# Controller-Sheet.net
KiCad netlist of a schematic drawn in Altium Designer
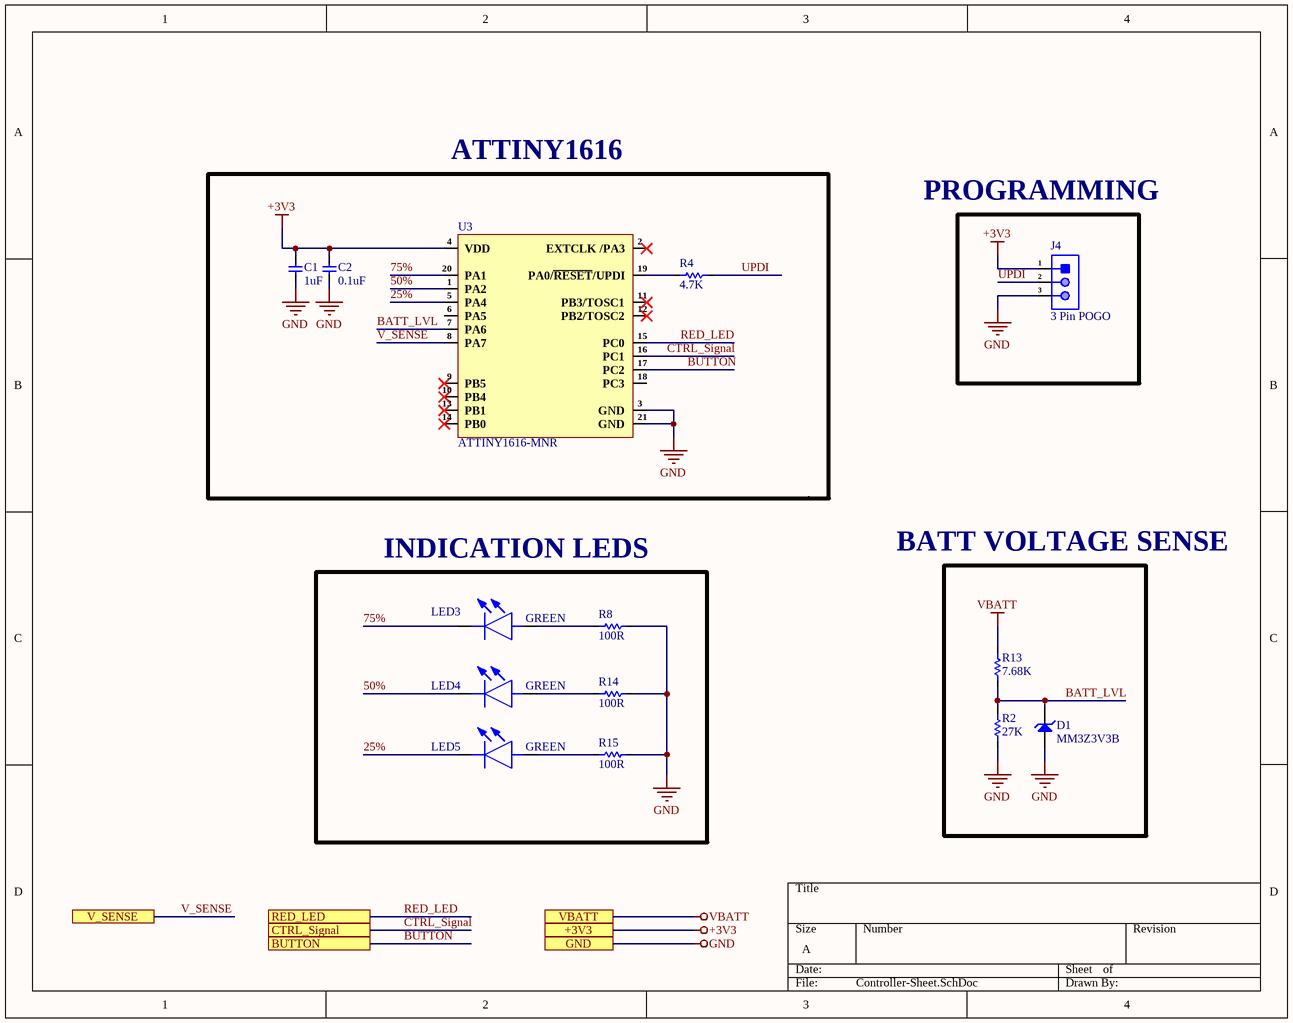
[diagram p0: Controller-Sheet.SchDoc]

(export (version "E")
  (design (tool "Eeschema 10.0.6"))
  (components
    (comp (ref "C1")
      (value "1uF")
      (footprint "Cap-0402")
      (description "1 µF ±20% 6.3V Ceramic Capacitor X5R 0201 (0603 Metric)")
      (fields
        (field (name "MANUFACTURER") "Murata Electronics")
        (field (name "MANUFACTURER PART NUMBER") "GRM033R60J105MEA2D")
      )
      (libsource (lib "LED-Driver-Library") (part "GRM033R60J105MEA2D"))
    )
    (comp (ref "C2")
      (value "0.1uF")
      (footprint "Cap-0402")
      (description "0.1 µF ±10% 16V Ceramic Capacitor X7R 0402 (1005 Metric)")
      (fields
        (field (name "MANUFACTURER") "Murata Electronics")
        (field (name "MANUFACTURER PART NUMBER") "GRM155R71C104KA88J")
      )
      (libsource (lib "LED-Driver-Library") (part "GRM155R71C104KA88J"))
    )
    (comp (ref "D1")
      (value "MM3Z3V3B")
      (footprint "SOD323F")
      (description "DIODE ZENER 3.3V 200MW SOD323F")
      (fields (field (name "MANUFACTURER") "ON Semiconductor / Fairchild") (field (name "TOLERANCE") "2%"))
      (libsource (lib "LED-Driver-Library") (part "MM3Z3V3B"))
    )
    (comp (ref "J4")
      (value "3 Pin POGO")
      (footprint "3 Pin POGO")
      (description "CONN HEADER VERT 3POS 2.54MM")
      (fields (field (name "LCSC PART NUMBER") "C168677") (field (name "DIGIKEY PART NUMBER") "609-3461-ND"))
      (libsource (lib "LED-Driver-Library") (part "68000-103HLF"))
    )
    (comp (ref "LED3")
      (value "GREEN")
      (footprint "150060GS75000")
      (description "Green 520nm LED Indication - Discrete 3.2V 0603 (1608 Metric)")
      (fields
        (field (name "MANUFACTURER") "Würth Elektronik")
        (field (name "MANUFACTURER PART NUMBER") "150060GS75000")
      )
      (libsource (lib "LED-Driver-Library") (part "150060GS75000"))
    )
    (comp (ref "LED4")
      (value "GREEN")
      (footprint "150060GS75000")
      (description "Green 520nm LED Indication - Discrete 3.2V 0603 (1608 Metric)")
      (fields
        (field (name "MANUFACTURER") "Würth Elektronik")
        (field (name "MANUFACTURER PART NUMBER") "150060GS75000")
      )
      (libsource (lib "LED-Driver-Library") (part "150060GS75000"))
    )
    (comp (ref "LED5")
      (value "GREEN")
      (footprint "150060GS75000")
      (description "Green 520nm LED Indication - Discrete 3.2V 0603 (1608 Metric)")
      (fields
        (field (name "MANUFACTURER") "Würth Elektronik")
        (field (name "MANUFACTURER PART NUMBER") "150060GS75000")
      )
      (libsource (lib "LED-Driver-Library") (part "150060GS75000"))
    )
    (comp (ref "R2")
      (value "27K")
      (footprint "Res-0402")
      (description "27 kOhms ±1% 0.063W, 1/16W Chip Resistor 0402 (1005 Metric) Moisture Resistant Thick Film")
      (fields
        (field (name "MANUFACTURER") "YAGEO")
        (field (name "MANUFACTURER PART NUMBER") "RC0402FR-0727KL")
      )
      (libsource (lib "LED-Driver-Library") (part "RC0402FR-0727KL"))
    )
    (comp (ref "R4")
      (value "4.7K")
      (footprint "Res-0402")
      (description "4.7 kOhms ±1% 0.063W, 1/16W Chip Resistor 0402 (1005 Metric) Moisture Resistant Thick Film")
      (fields
        (field (name "MANUFACTURER") "YAGEO")
        (field (name "MANUFACTURER PART NUMBER") "RC0402FR-074K7L")
      )
      (libsource (lib "LED-Driver-Library") (part "RC0402FR-074K7L"))
    )
    (comp (ref "R8")
      (value "100R")
      (footprint "Res-0402")
      (description "100 Ohms ±1% 0.063W, 1/16W Chip Resistor 0402 (1005 Metric) Moisture Resistant Thick Film")
      (fields
        (field (name "MANUFACTURER") "YAGEO")
        (field (name "MANUFACTURER PART NUMBER") "RC0402FR-07100RL")
      )
      (libsource (lib "LED-Driver-Library") (part "RC0402FR-07100RL"))
    )
    (comp (ref "R13")
      (value "7.68K")
      (footprint "Res-0402")
      (fields
        (field (name "MANUFACTURER") "YAGEO")
        (field (name "MANUFACTURER PART NUMBER") "AC0402FR-077K68L")
        (field (name "DIGIKEY PART NUMBER") "YAG5688DKR-ND")
      )
      (libsource (lib "LED-Driver-Library") (part "AC0402FR-077K68L"))
    )
    (comp (ref "R14")
      (value "100R")
      (footprint "Res-0402")
      (description "100 Ohms ±1% 0.063W, 1/16W Chip Resistor 0402 (1005 Metric) Moisture Resistant Thick Film")
      (fields
        (field (name "MANUFACTURER") "YAGEO")
        (field (name "MANUFACTURER PART NUMBER") "RC0402FR-07100RL")
      )
      (libsource (lib "LED-Driver-Library") (part "RC0402FR-07100RL"))
    )
    (comp (ref "R15")
      (value "100R")
      (footprint "Res-0402")
      (description "100 Ohms ±1% 0.063W, 1/16W Chip Resistor 0402 (1005 Metric) Moisture Resistant Thick Film")
      (fields
        (field (name "MANUFACTURER") "YAGEO")
        (field (name "MANUFACTURER PART NUMBER") "RC0402FR-07100RL")
      )
      (libsource (lib "LED-Driver-Library") (part "RC0402FR-07100RL"))
    )
    (comp (ref "U3")
      (value "ATTINY1616-MNR")
      (footprint "20-VQFN (3x3)")
      (fields
        (field (name "MANUFACTURER") "Microchip Tech")
        (field (name "DIGIKEY PART NUMBER") "ATTINY1616-MNRDKR-ND")
      )
      (libsource (lib "LED-Driver-Library") (part "ATTINY1616-MNR"))
    )
  )
  (nets
    (net (code "1") (name "+3V3") (class "Default")
      (node (ref "C1") (pin "2") (pinfunction "2_2") (pintype "passive"))
      (node (ref "C2") (pin "2") (pinfunction "2_2") (pintype "passive"))
      (node (ref "J4") (pin "1") (pinfunction "1_1") (pintype "passive"))
      (node (ref "U3") (pin "4") (pinfunction "VDD_4") (pintype "passive"))
    )
    (net (code "2") (name "/25%") (class "Default")
      (node (ref "LED5") (pin "1") (pinfunction "1_1") (pintype "passive"))
      (node (ref "U3") (pin "5") (pinfunction "PA4_5") (pintype "passive"))
    )
    (net (code "3") (name "/50%") (class "Default")
      (node (ref "LED4") (pin "1") (pinfunction "1_1") (pintype "passive"))
      (node (ref "U3") (pin "1") (pinfunction "PA2_1") (pintype "passive"))
    )
    (net (code "4") (name "/75%") (class "Default")
      (node (ref "LED3") (pin "1") (pinfunction "1_1") (pintype "passive"))
      (node (ref "U3") (pin "20") (pinfunction "PA1_20") (pintype "passive"))
    )
    (net (code "5") (name "/BATT_LVL") (class "Default")
      (node (ref "D1") (pin "2") (pinfunction "K_2") (pintype "passive"))
      (node (ref "R13") (pin "1") (pinfunction "1_1") (pintype "passive"))
      (node (ref "R2") (pin "2") (pinfunction "2_2") (pintype "passive"))
      (node (ref "U3") (pin "7") (pinfunction "PA6_7") (pintype "passive"))
    )
    (net (code "6") (name "/BUTTON") (class "Default")
      (node (ref "U3") (pin "17") (pinfunction "PC2_17") (pintype "passive"))
    )
    (net (code "7") (name "/CTRL_Signal") (class "Default")
      (node (ref "U3") (pin "16") (pinfunction "PC1_16") (pintype "passive"))
    )
    (net (code "8") (name "/RED_LED") (class "Default")
      (node (ref "U3") (pin "15") (pinfunction "PC0_15") (pintype "passive"))
    )
    (net (code "9") (name "/UPDI") (class "Default")
      (node (ref "J4") (pin "2") (pinfunction "2_2") (pintype "passive"))
      (node (ref "R4") (pin "2") (pinfunction "2_2") (pintype "passive"))
    )
    (net (code "10") (name "/V_SENSE") (class "Default")
      (node (ref "U3") (pin "8") (pinfunction "PA7_8") (pintype "passive"))
    )
    (net (code "11") (name "GND") (class "Default")
      (node (ref "C1") (pin "1") (pinfunction "1_1") (pintype "passive"))
      (node (ref "C2") (pin "1") (pinfunction "1_1") (pintype "passive"))
      (node (ref "D1") (pin "1") (pinfunction "A_1") (pintype "passive"))
      (node (ref "J4") (pin "3") (pinfunction "3_3") (pintype "passive"))
      (node (ref "R14") (pin "2") (pinfunction "2_2") (pintype "passive"))
      (node (ref "R15") (pin "2") (pinfunction "2_2") (pintype "passive"))
      (node (ref "R2") (pin "1") (pinfunction "1_1") (pintype "passive"))
      (node (ref "R8") (pin "2") (pinfunction "2_2") (pintype "passive"))
      (node (ref "U3") (pin "21") (pinfunction "GND_21") (pintype "passive"))
      (node (ref "U3") (pin "3") (pinfunction "GND_3") (pintype "passive"))
    )
    (net (code "12") (name "Net-(LED3-Pad2)") (class "Default")
      (node (ref "LED3") (pin "2") (pinfunction "2_2") (pintype "passive"))
      (node (ref "R8") (pin "1") (pinfunction "1_1") (pintype "passive"))
    )
    (net (code "13") (name "Net-(LED4-Pad2)") (class "Default")
      (node (ref "LED4") (pin "2") (pinfunction "2_2") (pintype "passive"))
      (node (ref "R14") (pin "1") (pinfunction "1_1") (pintype "passive"))
    )
    (net (code "14") (name "Net-(LED5-Pad2)") (class "Default")
      (node (ref "LED5") (pin "2") (pinfunction "2_2") (pintype "passive"))
      (node (ref "R15") (pin "1") (pinfunction "1_1") (pintype "passive"))
    )
    (net (code "15") (name "Net-(U3-PA0{slash}~{RESET}{slash}UPDI)") (class "Default")
      (node (ref "R4") (pin "1") (pinfunction "1_1") (pintype "passive"))
      (node (ref "U3") (pin "19") (pinfunction "PA0/~{RESET}/UPDI_19") (pintype "passive"))
    )
    (net (code "16") (name "VBATT") (class "Default")
      (node (ref "R13") (pin "2") (pinfunction "2_2") (pintype "passive"))
    )
    (net (code "17") (name "unconnected-(U3-EXTCLK_{slash}PA3-Pad2)") (class "Default")
      (node (ref "U3") (pin "2") (pinfunction "EXTCLK_/PA3_2") (pintype "passive+no_connect"))
    )
    (net (code "18") (name "unconnected-(U3-PA5-Pad6)") (class "Default")
      (node (ref "U3") (pin "6") (pinfunction "PA5_6") (pintype "passive"))
    )
    (net (code "19") (name "unconnected-(U3-PB0-Pad14)") (class "Default")
      (node (ref "U3") (pin "14") (pinfunction "PB0_14") (pintype "passive+no_connect"))
    )
    (net (code "20") (name "unconnected-(U3-PB1-Pad13)") (class "Default")
      (node (ref "U3") (pin "13") (pinfunction "PB1_13") (pintype "passive+no_connect"))
    )
    (net (code "21") (name "unconnected-(U3-PB2{slash}TOSC2-Pad12)") (class "Default")
      (node (ref "U3") (pin "12") (pinfunction "PB2/TOSC2_12") (pintype "passive+no_connect"))
    )
    (net (code "22") (name "unconnected-(U3-PB3{slash}TOSC1-Pad11)") (class "Default")
      (node (ref "U3") (pin "11") (pinfunction "PB3/TOSC1_11") (pintype "passive+no_connect"))
    )
    (net (code "23") (name "unconnected-(U3-PB4-Pad10)") (class "Default")
      (node (ref "U3") (pin "10") (pinfunction "PB4_10") (pintype "passive+no_connect"))
    )
    (net (code "24") (name "unconnected-(U3-PB5-Pad9)") (class "Default")
      (node (ref "U3") (pin "9") (pinfunction "PB5_9") (pintype "passive+no_connect"))
    )
    (net (code "25") (name "unconnected-(U3-PC3-Pad18)") (class "Default")
      (node (ref "U3") (pin "18") (pinfunction "PC3_18") (pintype "passive"))
    )
  )
)
